# UD3_1_PSOC.net
KiCad netlist of a schematic drawn in Altium Designer
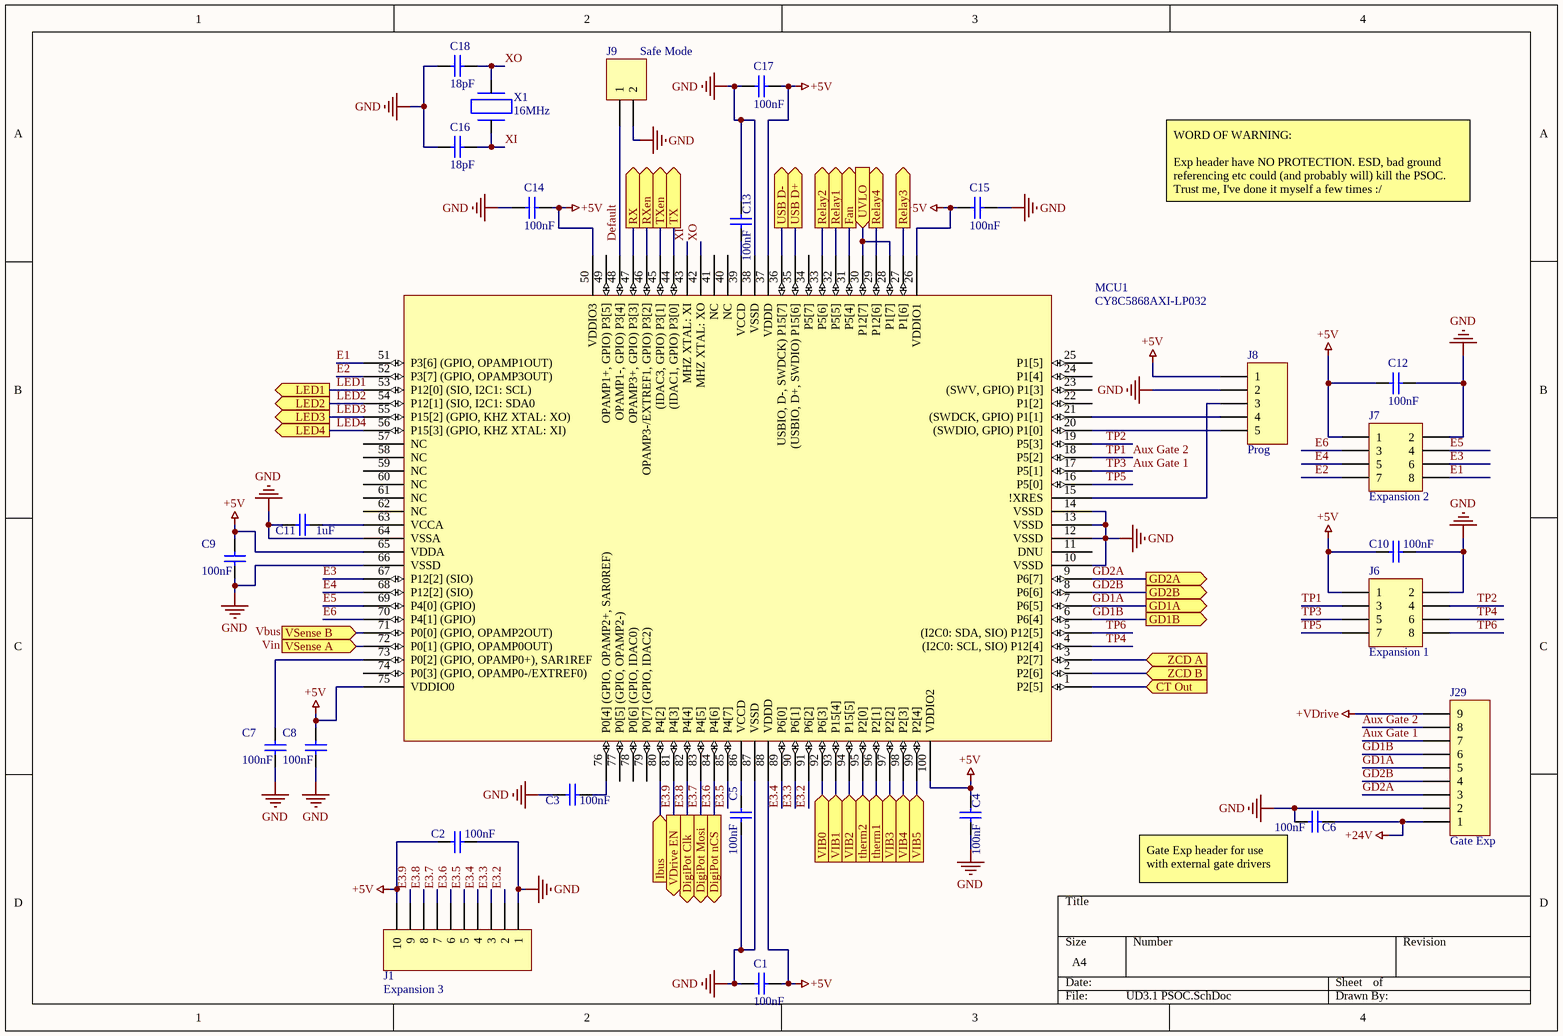
[diagram p0: UD3.1 PSOC.SchDoc]

(export (version "E")
  (design (tool "Eeschema 10.0.6"))
  (components
    (comp (ref "C1") (value "100nF") (footprint "0603") (libsource (lib "stdLib") (part "Cap")))
    (comp (ref "C2") (value "100nF") (footprint "0603") (libsource (lib "stdLib") (part "Cap")))
    (comp (ref "C3") (value "100nF") (footprint "0603") (libsource (lib "stdLib") (part "Cap")))
    (comp (ref "C4") (value "100nF") (footprint "0603") (libsource (lib "stdLib") (part "Cap")))
    (comp (ref "C5") (value "100nF") (footprint "0603") (libsource (lib "stdLib") (part "Cap")))
    (comp (ref "C6") (value "100nF") (footprint "0603") (libsource (lib "stdLib") (part "Cap")))
    (comp (ref "C7") (value "100nF") (footprint "0603") (libsource (lib "stdLib") (part "Cap")))
    (comp (ref "C8") (value "100nF") (footprint "0603") (libsource (lib "stdLib") (part "Cap")))
    (comp (ref "C9") (value "100nF") (footprint "0603") (libsource (lib "stdLib") (part "Cap")))
    (comp (ref "C10") (value "100nF") (footprint "0603") (libsource (lib "stdLib") (part "Cap")))
    (comp (ref "C11") (value "1uF") (footprint "0603") (libsource (lib "stdLib") (part "Cap")))
    (comp (ref "C12") (value "100nF") (footprint "0603") (libsource (lib "stdLib") (part "Cap")))
    (comp (ref "C13") (value "100nF") (footprint "0603") (libsource (lib "stdLib") (part "Cap")))
    (comp (ref "C14") (value "100nF") (footprint "0603") (libsource (lib "stdLib") (part "Cap")))
    (comp (ref "C15") (value "100nF") (footprint "0603") (libsource (lib "stdLib") (part "Cap")))
    (comp (ref "C16") (value "18pF") (footprint "0603") (libsource (lib "stdLib") (part "Cap")))
    (comp (ref "C17") (value "100nF") (footprint "0603") (libsource (lib "stdLib") (part "Cap")))
    (comp (ref "C18") (value "18pF") (footprint "0603") (libsource (lib "stdLib") (part "Cap")))
    (comp (ref "J1")
      (value "Expansion 3")
      (footprint "HDR1X10")
      (description "Header, 10-Pin")
      (fields (field (name "PUBLISHER") "Altium Limited"))
      (libsource (lib "Miscellaneous Connectors") (part "Header 10"))
    )
    (comp (ref "J6")
      (value "Expansion 1")
      (footprint "HDR2X4")
      (description "Header, 4-Pin, Dual row")
      (fields (field (name "PUBLISHER") "Altium Limited"))
      (libsource (lib "Miscellaneous Connectors") (part "Header 4X2"))
    )
    (comp (ref "J7")
      (value "Expansion 2")
      (footprint "HDR2X4")
      (description "Header, 4-Pin, Dual row")
      (fields (field (name "PUBLISHER") "Altium Limited"))
      (libsource (lib "Miscellaneous Connectors") (part "Header 4X2"))
    )
    (comp (ref "J8")
      (value "Prog")
      (footprint "HDR1X5")
      (description "Header, 5-Pin")
      (fields (field (name "PUBLISHER") "Altium Limited"))
      (libsource (lib "Miscellaneous Connectors") (part "Header 5"))
    )
    (comp (ref "J9")
      (value "Safe Mode")
      (footprint "HDR1X2")
      (description "Header, 2-Pin")
      (fields (field (name "PUBLISHER") "Altium Limited"))
      (libsource (lib "Miscellaneous Connectors") (part "Header 2"))
    )
    (comp (ref "J29")
      (value "Gate Exp")
      (footprint "HDR1X9")
      (description "Header, 9-Pin")
      (fields (field (name "PUBLISHER") "Altium Limited"))
      (libsource (lib "Miscellaneous Connectors") (part "Header 9"))
    )
    (comp (ref "MCU1")
      (value "CY8C5868AXI-LP032")
      (footprint "TQFP 100")
      (libsource (lib "steve lib") (part "CY8C5466AXI-064"))
    )
    (comp (ref "X1")
      (value "16MHz")
      (footprint "ECS-3225MV Oscillator")
      (libsource (lib "stdLib") (part "Quarz crystal"))
    )
  )
  (nets
    (net (code "1") (name "+5V") (class "Default")
      (node (ref "C1") (pin "2") (pinfunction "2_2") (pintype "passive"))
      (node (ref "C10") (pin "1") (pinfunction "1_1") (pintype "passive"))
      (node (ref "C12") (pin "2") (pinfunction "2_2") (pintype "passive"))
      (node (ref "C14") (pin "2") (pinfunction "2_2") (pintype "passive"))
      (node (ref "C15") (pin "2") (pinfunction "2_2") (pintype "passive"))
      (node (ref "C17") (pin "2") (pinfunction "2_2") (pintype "passive"))
      (node (ref "C2") (pin "1") (pinfunction "1_1") (pintype "passive"))
      (node (ref "C4") (pin "2") (pinfunction "2_2") (pintype "passive"))
      (node (ref "C8") (pin "2") (pinfunction "2_2") (pintype "passive"))
      (node (ref "C9") (pin "2") (pinfunction "2_2") (pintype "passive"))
      (node (ref "J1") (pin "10") (pinfunction "10_10") (pintype "passive"))
      (node (ref "J6") (pin "1") (pinfunction "1_1") (pintype "passive"))
      (node (ref "J7") (pin "1") (pinfunction "1_1") (pintype "passive"))
      (node (ref "J8") (pin "1") (pinfunction "1_1") (pintype "passive"))
      (node (ref "MCU1") (pin "100") (pinfunction "VDDIO2_100") (pintype "passive"))
      (node (ref "MCU1") (pin "26") (pinfunction "VDDIO1_26") (pintype "power_in"))
      (node (ref "MCU1") (pin "37") (pinfunction "VDDD_37") (pintype "power_in"))
      (node (ref "MCU1") (pin "50") (pinfunction "VDDIO3_50") (pintype "power_in"))
      (node (ref "MCU1") (pin "65") (pinfunction "VDDA_65") (pintype "power_in"))
      (node (ref "MCU1") (pin "75") (pinfunction "VDDIO0_75") (pintype "power_in"))
      (node (ref "MCU1") (pin "88") (pinfunction "VDDD_88") (pintype "power_in"))
    )
    (net (code "2") (name "+24V") (class "Default")
      (node (ref "C6") (pin "2") (pinfunction "2_2") (pintype "passive"))
      (node (ref "J29") (pin "1") (pinfunction "1_1") (pintype "passive"))
    )
    (net (code "3") (name "+VDrive") (class "Default")
      (node (ref "J29") (pin "9") (pinfunction "9_9") (pintype "passive"))
    )
    (net (code "4") (name "/Aux Gate 1") (class "Default")
      (node (ref "J29") (pin "7") (pinfunction "7_7") (pintype "passive"))
      (node (ref "J6") (pin "5") (pinfunction "5_5") (pintype "passive"))
      (node (ref "MCU1") (pin "17") (pinfunction "P5[1]_17") (pintype "bidirectional"))
    )
    (net (code "5") (name "/Aux Gate 2") (class "Default")
      (node (ref "J29") (pin "8") (pinfunction "8_8") (pintype "passive"))
      (node (ref "J6") (pin "3") (pinfunction "3_3") (pintype "passive"))
      (node (ref "MCU1") (pin "18") (pinfunction "P5[2]_18") (pintype "bidirectional"))
    )
    (net (code "6") (name "/CT Out") (class "Default")
      (node (ref "MCU1") (pin "1") (pinfunction "P2[5]_1") (pintype "bidirectional"))
    )
    (net (code "7") (name "/Default") (class "Default")
      (node (ref "J9") (pin "1") (pinfunction "1_1") (pintype "passive"))
      (node (ref "MCU1") (pin "48") (pinfunction "OPAMP1-,_GPIO)_P3[4]_48") (pintype "bidirectional"))
    )
    (net (code "8") (name "/E1") (class "Default")
      (node (ref "J7") (pin "8") (pinfunction "8_8") (pintype "passive"))
      (node (ref "MCU1") (pin "51") (pinfunction "P3[6]_(GPIO,_OPAMP1OUT)_51") (pintype "bidirectional"))
    )
    (net (code "9") (name "/E2") (class "Default")
      (node (ref "J7") (pin "7") (pinfunction "7_7") (pintype "passive"))
      (node (ref "MCU1") (pin "52") (pinfunction "P3[7]_(GPIO,_OPAMP3OUT)_52") (pintype "bidirectional"))
    )
    (net (code "10") (name "/E3") (class "Default")
      (node (ref "J7") (pin "6") (pinfunction "6_6") (pintype "passive"))
      (node (ref "MCU1") (pin "67") (pinfunction "P12[2]_(SIO)_67") (pintype "bidirectional"))
    )
    (net (code "11") (name "/E3.2") (class "Default")
      (node (ref "J1") (pin "2") (pinfunction "2_2") (pintype "passive"))
      (node (ref "MCU1") (pin "91") (pinfunction "P6[2]_91") (pintype "bidirectional"))
    )
    (net (code "12") (name "/E3.3") (class "Default")
      (node (ref "J1") (pin "3") (pinfunction "3_3") (pintype "passive"))
      (node (ref "MCU1") (pin "90") (pinfunction "P6[1]_90") (pintype "bidirectional"))
    )
    (net (code "13") (name "/E3.4") (class "Default")
      (node (ref "J1") (pin "4") (pinfunction "4_4") (pintype "passive"))
      (node (ref "MCU1") (pin "89") (pinfunction "P6[0]_89") (pintype "bidirectional"))
    )
    (net (code "14") (name "/E3.5") (class "Default")
      (node (ref "J1") (pin "5") (pinfunction "5_5") (pintype "passive"))
      (node (ref "MCU1") (pin "85") (pinfunction "P4[7]_85") (pintype "bidirectional"))
    )
    (net (code "15") (name "/E3.6") (class "Default")
      (node (ref "J1") (pin "6") (pinfunction "6_6") (pintype "passive"))
      (node (ref "MCU1") (pin "84") (pinfunction "P4[6]_84") (pintype "bidirectional"))
    )
    (net (code "16") (name "/E3.7") (class "Default")
      (node (ref "J1") (pin "7") (pinfunction "7_7") (pintype "passive"))
      (node (ref "MCU1") (pin "83") (pinfunction "P4[5]_83") (pintype "bidirectional"))
    )
    (net (code "17") (name "/E3.8") (class "Default")
      (node (ref "J1") (pin "8") (pinfunction "8_8") (pintype "passive"))
      (node (ref "MCU1") (pin "82") (pinfunction "P4[4]_82") (pintype "bidirectional"))
    )
    (net (code "18") (name "/E3.9") (class "Default")
      (node (ref "J1") (pin "9") (pinfunction "9_9") (pintype "passive"))
      (node (ref "MCU1") (pin "81") (pinfunction "P4[3]_81") (pintype "bidirectional"))
    )
    (net (code "19") (name "/E4") (class "Default")
      (node (ref "J7") (pin "5") (pinfunction "5_5") (pintype "passive"))
      (node (ref "MCU1") (pin "68") (pinfunction "P12[2]_(SIO)_68") (pintype "bidirectional"))
    )
    (net (code "20") (name "/E5") (class "Default")
      (node (ref "J7") (pin "4") (pinfunction "4_4") (pintype "passive"))
      (node (ref "MCU1") (pin "69") (pinfunction "P4[0]_(GPIO)_69") (pintype "bidirectional"))
    )
    (net (code "21") (name "/E6") (class "Default")
      (node (ref "J7") (pin "3") (pinfunction "3_3") (pintype "passive"))
      (node (ref "MCU1") (pin "70") (pinfunction "P4[1]_(GPIO)_70") (pintype "bidirectional"))
    )
    (net (code "22") (name "/Fan") (class "Default")
      (node (ref "MCU1") (pin "31") (pinfunction "P5[4]_31") (pintype "bidirectional"))
    )
    (net (code "23") (name "/GD1A") (class "Default")
      (node (ref "J29") (pin "5") (pinfunction "5_5") (pintype "passive"))
      (node (ref "MCU1") (pin "7") (pinfunction "P6[5]_7") (pintype "bidirectional"))
    )
    (net (code "24") (name "/GD1B") (class "Default")
      (node (ref "J29") (pin "6") (pinfunction "6_6") (pintype "passive"))
      (node (ref "MCU1") (pin "6") (pinfunction "P6[4]_6") (pintype "bidirectional"))
    )
    (net (code "25") (name "/GD2A") (class "Default")
      (node (ref "J29") (pin "3") (pinfunction "3_3") (pintype "passive"))
      (node (ref "MCU1") (pin "9") (pinfunction "P6[7]_9") (pintype "bidirectional"))
    )
    (net (code "26") (name "/GD2B") (class "Default")
      (node (ref "J29") (pin "4") (pinfunction "4_4") (pintype "passive"))
      (node (ref "MCU1") (pin "8") (pinfunction "P6[6]_8") (pintype "bidirectional"))
    )
    (net (code "27") (name "/Ibus") (class "Default")
      (node (ref "MCU1") (pin "80") (pinfunction "P4[2]_80") (pintype "bidirectional"))
    )
    (net (code "28") (name "/LED1") (class "Default")
      (node (ref "MCU1") (pin "53") (pinfunction "P12[0]_(SIO,_I2C1:_SCL)_53") (pintype "bidirectional"))
    )
    (net (code "29") (name "/LED2") (class "Default")
      (node (ref "MCU1") (pin "54") (pinfunction "P12[1]_(SIO,_I2C1:_SDA0_54") (pintype "bidirectional"))
    )
    (net (code "30") (name "/LED3") (class "Default")
      (node (ref "MCU1") (pin "55") (pinfunction "P15[2]_(GPIO,_KHZ_XTAL:_XO)_55") (pintype "bidirectional"))
    )
    (net (code "31") (name "/LED4") (class "Default")
      (node (ref "MCU1") (pin "56") (pinfunction "P15[3]_(GPIO,_KHZ_XTAL:_XI)_56") (pintype "bidirectional"))
    )
    (net (code "32") (name "/RX") (class "Default")
      (node (ref "MCU1") (pin "47") (pinfunction "OPAMP3+,_GPIO)_P3[3]_47") (pintype "bidirectional"))
    )
    (net (code "33") (name "/RXen") (class "Default")
      (node (ref "MCU1") (pin "46") (pinfunction "OPAMP3-/EXTREF1,_GPIO)_P3[2]_46") (pintype "bidirectional"))
    )
    (net (code "34") (name "/Relay1") (class "Default")
      (node (ref "MCU1") (pin "32") (pinfunction "P5[5]_32") (pintype "bidirectional"))
    )
    (net (code "35") (name "/Relay2") (class "Default")
      (node (ref "MCU1") (pin "33") (pinfunction "P5[6]_33") (pintype "bidirectional"))
    )
    (net (code "36") (name "/Relay3") (class "Default")
      (node (ref "MCU1") (pin "27") (pinfunction "P1[6]_27") (pintype "bidirectional"))
    )
    (net (code "37") (name "/Relay4") (class "Default")
      (node (ref "MCU1") (pin "29") (pinfunction "P12[6]_29") (pintype "bidirectional"))
    )
    (net (code "38") (name "/TP2") (class "Default")
      (node (ref "J6") (pin "4") (pinfunction "4_4") (pintype "passive"))
      (node (ref "MCU1") (pin "19") (pinfunction "P5[3]_19") (pintype "bidirectional"))
    )
    (net (code "39") (name "/TP4") (class "Default")
      (node (ref "J6") (pin "6") (pinfunction "6_6") (pintype "passive"))
      (node (ref "MCU1") (pin "4") (pinfunction "(I2C0:_SCL,_SIO)_P12[4]_4") (pintype "bidirectional"))
    )
    (net (code "40") (name "/TP5") (class "Default")
      (node (ref "J6") (pin "7") (pinfunction "7_7") (pintype "passive"))
      (node (ref "MCU1") (pin "16") (pinfunction "P5[0]_16") (pintype "bidirectional"))
    )
    (net (code "41") (name "/TP6") (class "Default")
      (node (ref "J6") (pin "8") (pinfunction "8_8") (pintype "passive"))
      (node (ref "MCU1") (pin "5") (pinfunction "(I2C0:_SDA,_SIO)_P12[5]_5") (pintype "bidirectional"))
    )
    (net (code "42") (name "/TX") (class "Default")
      (node (ref "MCU1") (pin "44") (pinfunction "(IDAC1,_GPIO)_P3[0]_44") (pintype "bidirectional"))
    )
    (net (code "43") (name "/TXen") (class "Default")
      (node (ref "MCU1") (pin "45") (pinfunction "(IDAC3,_GPIO)_P3[1]_45") (pintype "bidirectional"))
    )
    (net (code "44") (name "/USB D+") (class "Default")
      (node (ref "MCU1") (pin "35") (pinfunction "(USBIO,_D+,_SWDIO)_P15[6]_35") (pintype "bidirectional"))
    )
    (net (code "45") (name "/USB D-") (class "Default")
      (node (ref "MCU1") (pin "36") (pinfunction "USBIO,_D-,_SWDCK)_P15[7]_36") (pintype "bidirectional"))
    )
    (net (code "46") (name "/UVLO") (class "Default")
      (node (ref "MCU1") (pin "28") (pinfunction "P1[7]_28") (pintype "bidirectional"))
      (node (ref "MCU1") (pin "30") (pinfunction "P12[7]_30") (pintype "bidirectional"))
    )
    (net (code "47") (name "/VIB0") (class "Default")
      (node (ref "MCU1") (pin "92") (pinfunction "P6[3]_92") (pintype "bidirectional"))
    )
    (net (code "48") (name "/VIB1") (class "Default")
      (node (ref "MCU1") (pin "93") (pinfunction "P15[4]_93") (pintype "bidirectional"))
    )
    (net (code "49") (name "/VIB2") (class "Default")
      (node (ref "MCU1") (pin "94") (pinfunction "P15[5]_94") (pintype "bidirectional"))
    )
    (net (code "50") (name "/VIB3") (class "Default")
      (node (ref "MCU1") (pin "97") (pinfunction "P2[2]_97") (pintype "bidirectional"))
    )
    (net (code "51") (name "/VIB4") (class "Default")
      (node (ref "MCU1") (pin "98") (pinfunction "P2[3]_98") (pintype "bidirectional"))
    )
    (net (code "52") (name "/VIB5") (class "Default")
      (node (ref "MCU1") (pin "99") (pinfunction "P2[4]_99") (pintype "bidirectional"))
    )
    (net (code "53") (name "/VSense A") (class "Default")
      (node (ref "MCU1") (pin "72") (pinfunction "P0[1]_(GPIO,_OPAMP0OUT)_72") (pintype "bidirectional"))
    )
    (net (code "54") (name "/VSense B") (class "Default")
      (node (ref "MCU1") (pin "71") (pinfunction "P0[0]_(GPIO,_OPAMP2OUT)_71") (pintype "bidirectional"))
    )
    (net (code "57") (name "/XI") (class "Default")
      (node (ref "C16") (pin "1") (pinfunction "1_1") (pintype "passive"))
      (node (ref "MCU1") (pin "43") (pinfunction "MHZ_XTAL:_XI_43") (pintype "passive"))
      (node (ref "X1") (pin "2") (pinfunction "24_2") (pintype "passive"))
    )
    (net (code "58") (name "/XO") (class "Default")
      (node (ref "C18") (pin "1") (pinfunction "1_1") (pintype "passive"))
      (node (ref "MCU1") (pin "42") (pinfunction "MHZ_XTAL:_XO_42") (pintype "passive"))
      (node (ref "X1") (pin "1") (pinfunction "23_1") (pintype "passive"))
    )
    (net (code "59") (name "/ZCD A") (class "Default")
      (node (ref "MCU1") (pin "3") (pinfunction "P2[7]_3") (pintype "bidirectional"))
    )
    (net (code "60") (name "/ZCD B") (class "Default")
      (node (ref "MCU1") (pin "2") (pinfunction "P2[6]_2") (pintype "bidirectional"))
    )
    (net (code "61") (name "/therm1") (class "Default")
      (node (ref "MCU1") (pin "96") (pinfunction "P2[1]_96") (pintype "bidirectional"))
    )
    (net (code "62") (name "/therm2") (class "Default")
      (node (ref "MCU1") (pin "95") (pinfunction "P2[0]_95") (pintype "bidirectional"))
    )
    (net (code "63") (name "GND") (class "Default")
      (node (ref "C1") (pin "1") (pinfunction "1_1") (pintype "passive"))
      (node (ref "C10") (pin "2") (pinfunction "2_2") (pintype "passive"))
      (node (ref "C11") (pin "1") (pinfunction "1_1") (pintype "passive"))
      (node (ref "C12") (pin "1") (pinfunction "1_1") (pintype "passive"))
      (node (ref "C13") (pin "1") (pinfunction "1_1") (pintype "passive"))
      (node (ref "C14") (pin "1") (pinfunction "1_1") (pintype "passive"))
      (node (ref "C15") (pin "1") (pinfunction "1_1") (pintype "passive"))
      (node (ref "C16") (pin "2") (pinfunction "2_2") (pintype "passive"))
      (node (ref "C17") (pin "1") (pinfunction "1_1") (pintype "passive"))
      (node (ref "C18") (pin "2") (pinfunction "2_2") (pintype "passive"))
      (node (ref "C2") (pin "2") (pinfunction "2_2") (pintype "passive"))
      (node (ref "C3") (pin "1") (pinfunction "1_1") (pintype "passive"))
      (node (ref "C4") (pin "1") (pinfunction "1_1") (pintype "passive"))
      (node (ref "C5") (pin "1") (pinfunction "1_1") (pintype "passive"))
      (node (ref "C6") (pin "1") (pinfunction "1_1") (pintype "passive"))
      (node (ref "C7") (pin "1") (pinfunction "1_1") (pintype "passive"))
      (node (ref "C8") (pin "1") (pinfunction "1_1") (pintype "passive"))
      (node (ref "C9") (pin "1") (pinfunction "1_1") (pintype "passive"))
      (node (ref "J1") (pin "1") (pinfunction "1_1") (pintype "passive"))
      (node (ref "J29") (pin "2") (pinfunction "2_2") (pintype "passive"))
      (node (ref "J6") (pin "2") (pinfunction "2_2") (pintype "passive"))
      (node (ref "J7") (pin "2") (pinfunction "2_2") (pintype "passive"))
      (node (ref "J8") (pin "2") (pinfunction "2_2") (pintype "passive"))
      (node (ref "J9") (pin "2") (pinfunction "2_2") (pintype "passive"))
      (node (ref "MCU1") (pin "10") (pinfunction "VSSD_10") (pintype "power_in"))
      (node (ref "MCU1") (pin "12") (pinfunction "VSSD_12") (pintype "power_in"))
      (node (ref "MCU1") (pin "13") (pinfunction "VSSD_13") (pintype "power_in"))
      (node (ref "MCU1") (pin "14") (pinfunction "VSSD_14") (pintype "power_in"))
      (node (ref "MCU1") (pin "38") (pinfunction "VSSD_38") (pintype "power_in"))
      (node (ref "MCU1") (pin "64") (pinfunction "VSSA_64") (pintype "power_in"))
      (node (ref "MCU1") (pin "66") (pinfunction "VSSD_66") (pintype "power_in"))
      (node (ref "MCU1") (pin "87") (pinfunction "VSSD_87") (pintype "power_in"))
    )
    (net (code "64") (name "Net-(C5-Pad2)") (class "Default")
      (node (ref "C5") (pin "2") (pinfunction "2_2") (pintype "passive"))
      (node (ref "MCU1") (pin "86") (pinfunction "VCCD_86") (pintype "power_in"))
    )
    (net (code "65") (name "Net-(C13-Pad2)") (class "Default")
      (node (ref "C13") (pin "2") (pinfunction "2_2") (pintype "passive"))
      (node (ref "MCU1") (pin "39") (pinfunction "VCCD_39") (pintype "power_in"))
    )
    (net (code "66") (name "Net-(MCU1-!XRES)") (class "Default")
      (node (ref "J8") (pin "3") (pinfunction "3_3") (pintype "passive"))
      (node (ref "MCU1") (pin "15") (pinfunction "!XRES_15") (pintype "passive"))
    )
    (net (code "67") (name "Net-(MCU1-(SWDCK,_GPIO)_P1[1])") (class "Default")
      (node (ref "J8") (pin "4") (pinfunction "4_4") (pintype "passive"))
      (node (ref "MCU1") (pin "21") (pinfunction "(SWDCK,_GPIO)_P1[1]_21") (pintype "bidirectional"))
    )
    (net (code "68") (name "Net-(MCU1-(SWDIO,_GPIO)_P1[0])") (class "Default")
      (node (ref "J8") (pin "5") (pinfunction "5_5") (pintype "passive"))
      (node (ref "MCU1") (pin "20") (pinfunction "(SWDIO,_GPIO)_P1[0]_20") (pintype "bidirectional"))
    )
    (net (code "69") (name "Net-(MCU1-P0[2]_(GPIO,_OPAMP0+),_SAR1REF)") (class "Default")
      (node (ref "C7") (pin "2") (pinfunction "2_2") (pintype "passive"))
      (node (ref "MCU1") (pin "73") (pinfunction "P0[2]_(GPIO,_OPAMP0+),_SAR1REF_73") (pintype "bidirectional"))
    )
    (net (code "70") (name "Net-(MCU1-P0[4]_(GPIO,_OPAMP2+,_SAR0REF))") (class "Default")
      (node (ref "C3") (pin "2") (pinfunction "2_2") (pintype "passive"))
      (node (ref "MCU1") (pin "76") (pinfunction "P0[4]_(GPIO,_OPAMP2+,_SAR0REF)_76") (pintype "bidirectional"))
    )
    (net (code "71") (name "Net-(MCU1-VCCA)") (class "Default")
      (node (ref "C11") (pin "2") (pinfunction "2_2") (pintype "passive"))
      (node (ref "MCU1") (pin "63") (pinfunction "VCCA_63") (pintype "power_in"))
    )
    (net (code "72") (name "unconnected-(MCU1-(SWV,_GPIO)_P1[3]-Pad23)") (class "Default")
      (node (ref "MCU1") (pin "23") (pinfunction "(SWV,_GPIO)_P1[3]_23") (pintype "bidirectional"))
    )
    (net (code "73") (name "unconnected-(MCU1-DNU-Pad11)") (class "Default")
      (node (ref "MCU1") (pin "11") (pinfunction "DNU_11") (pintype "passive"))
    )
    (net (code "74") (name "unconnected-(MCU1-NC-Pad40)") (class "Default")
      (node (ref "MCU1") (pin "40") (pinfunction "NC_40") (pintype "passive"))
    )
    (net (code "75") (name "unconnected-(MCU1-NC-Pad41)") (class "Default")
      (node (ref "MCU1") (pin "41") (pinfunction "NC_41") (pintype "passive"))
    )
    (net (code "76") (name "unconnected-(MCU1-NC-Pad57)") (class "Default")
      (node (ref "MCU1") (pin "57") (pinfunction "NC_57") (pintype "passive"))
    )
    (net (code "77") (name "unconnected-(MCU1-NC-Pad58)") (class "Default")
      (node (ref "MCU1") (pin "58") (pinfunction "NC_58") (pintype "passive"))
    )
    (net (code "78") (name "unconnected-(MCU1-NC-Pad59)") (class "Default")
      (node (ref "MCU1") (pin "59") (pinfunction "NC_59") (pintype "passive"))
    )
    (net (code "79") (name "unconnected-(MCU1-NC-Pad60)") (class "Default")
      (node (ref "MCU1") (pin "60") (pinfunction "NC_60") (pintype "passive"))
    )
    (net (code "80") (name "unconnected-(MCU1-NC-Pad61)") (class "Default")
      (node (ref "MCU1") (pin "61") (pinfunction "NC_61") (pintype "passive"))
    )
    (net (code "81") (name "unconnected-(MCU1-NC-Pad62)") (class "Default")
      (node (ref "MCU1") (pin "62") (pinfunction "NC_62") (pintype "passive"))
    )
    (net (code "82") (name "unconnected-(MCU1-OPAMP1+,_GPIO)_P3[5]-Pad49)") (class "Default")
      (node (ref "MCU1") (pin "49") (pinfunction "OPAMP1+,_GPIO)_P3[5]_49") (pintype "bidirectional"))
    )
    (net (code "83") (name "unconnected-(MCU1-P0[3]_(GPIO,_OPAMP0-{slash}EXTREF0)-Pad74)") (class "Default")
      (node (ref "MCU1") (pin "74") (pinfunction "P0[3]_(GPIO,_OPAMP0-/EXTREF0)_74") (pintype "bidirectional"))
    )
    (net (code "84") (name "unconnected-(MCU1-P0[5]_(GPIO,_OPAMP2-)-Pad77)") (class "Default")
      (node (ref "MCU1") (pin "77") (pinfunction "P0[5]_(GPIO,_OPAMP2-)_77") (pintype "bidirectional"))
    )
    (net (code "85") (name "unconnected-(MCU1-P0[6]_(GPIO,_IDAC0)-Pad78)") (class "Default")
      (node (ref "MCU1") (pin "78") (pinfunction "P0[6]_(GPIO,_IDAC0)_78") (pintype "bidirectional"))
    )
    (net (code "86") (name "unconnected-(MCU1-P0[7]_(GPIO,_IDAC2)-Pad79)") (class "Default")
      (node (ref "MCU1") (pin "79") (pinfunction "P0[7]_(GPIO,_IDAC2)_79") (pintype "bidirectional"))
    )
    (net (code "87") (name "unconnected-(MCU1-P1[2]-Pad22)") (class "Default")
      (node (ref "MCU1") (pin "22") (pinfunction "P1[2]_22") (pintype "bidirectional"))
    )
    (net (code "88") (name "unconnected-(MCU1-P1[4]-Pad24)") (class "Default")
      (node (ref "MCU1") (pin "24") (pinfunction "P1[4]_24") (pintype "bidirectional"))
    )
    (net (code "89") (name "unconnected-(MCU1-P1[5]-Pad25)") (class "Default")
      (node (ref "MCU1") (pin "25") (pinfunction "P1[5]_25") (pintype "bidirectional"))
    )
    (net (code "90") (name "unconnected-(MCU1-P5[7]-Pad34)") (class "Default")
      (node (ref "MCU1") (pin "34") (pinfunction "P5[7]_34") (pintype "bidirectional"))
    )
  )
)
